# scheda_mot.net
KiCad netlist of a schematic drawn in EAGLE
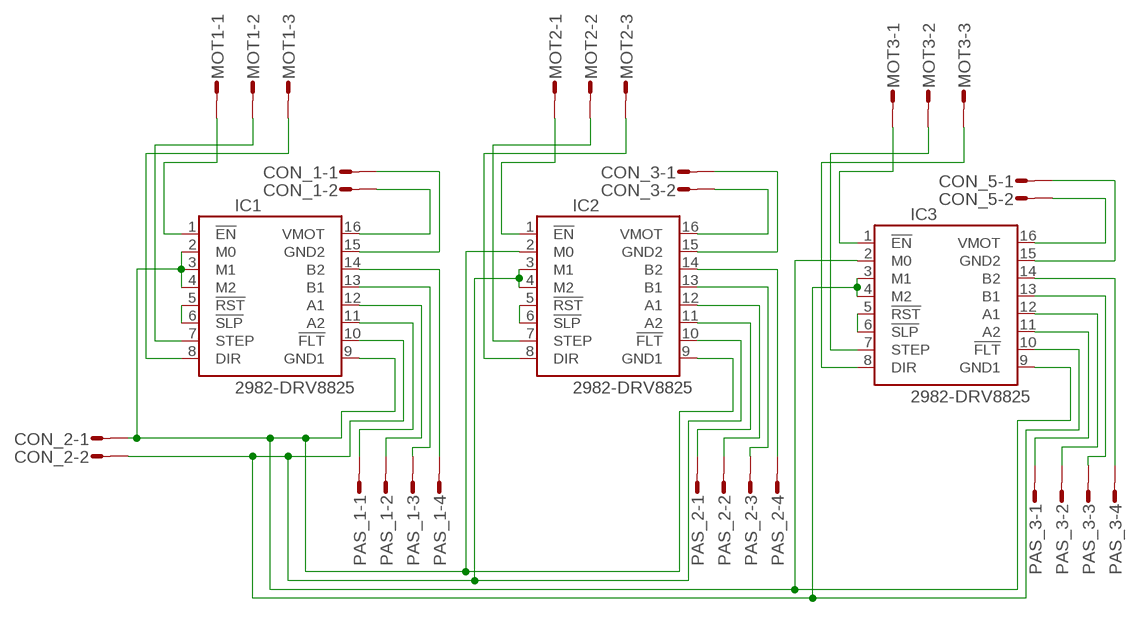
[diagram p0: schematic, sheet 1]

(export (version "E")
  (design (tool "Eeschema 10.0.6"))
  (components
    (comp (ref "CON_1")
      (value "S02P")
      (footprint "eagle-import:S02P")
      (libsource (lib "eagle-import") (part "S02P"))
    )
    (comp (ref "CON_2")
      (value "S02P")
      (footprint "eagle-import:S02P")
      (libsource (lib "eagle-import") (part "S02P"))
    )
    (comp (ref "CON_3")
      (value "S02P")
      (footprint "eagle-import:S02P")
      (libsource (lib "eagle-import") (part "S02P"))
    )
    (comp (ref "CON_5")
      (value "S02P")
      (footprint "eagle-import:S02P")
      (libsource (lib "eagle-import") (part "S02P"))
    )
    (comp (ref "IC1")
      (value "2982-DRV8825")
      (footprint "eagle-import:DRV8825")
      (libsource (lib "eagle-import") (part "2982-DRV8825"))
    )
    (comp (ref "IC2")
      (value "2982-DRV8825")
      (footprint "eagle-import:DRV8825")
      (libsource (lib "eagle-import") (part "2982-DRV8825"))
    )
    (comp (ref "IC3")
      (value "2982-DRV8825")
      (footprint "eagle-import:DRV8825")
      (libsource (lib "eagle-import") (part "2982-DRV8825"))
    )
    (comp (ref "MOT1")
      (value "S03P")
      (footprint "eagle-import:S03P")
      (libsource (lib "eagle-import") (part "S03P"))
    )
    (comp (ref "MOT2")
      (value "S03P")
      (footprint "eagle-import:S03P")
      (libsource (lib "eagle-import") (part "S03P"))
    )
    (comp (ref "MOT3")
      (value "S03P")
      (footprint "eagle-import:S03P")
      (libsource (lib "eagle-import") (part "S03P"))
    )
    (comp (ref "PAS_1")
      (value "S05P")
      (footprint "eagle-import:S05P")
      (libsource (lib "eagle-import") (part "S05P"))
    )
    (comp (ref "PAS_2")
      (value "S05P")
      (footprint "eagle-import:S05P")
      (libsource (lib "eagle-import") (part "S05P"))
    )
    (comp (ref "PAS_3")
      (value "S05P")
      (footprint "eagle-import:S05P")
      (libsource (lib "eagle-import") (part "S05P"))
    )
  )
  (nets
    (net (code "1") (name "Net-(CON_1A-S)") (class "Default")
      (node (ref "CON_1") (pin "1") (pinfunction "S_1") (pintype "passive"))
      (node (ref "IC1") (pin "15") (pinfunction "GND2_15") (pintype "power_in"))
    )
    (net (code "2") (name "Net-(CON_1B-S)") (class "Default")
      (node (ref "CON_1") (pin "2") (pinfunction "S_2") (pintype "passive"))
      (node (ref "IC1") (pin "16") (pinfunction "VMOT_16") (pintype "power_in"))
    )
    (net (code "3") (name "Net-(CON_2A-S)") (class "Default")
      (node (ref "CON_2") (pin "1") (pinfunction "S_1") (pintype "passive"))
      (node (ref "IC1") (pin "2") (pinfunction "M0_2") (pintype "passive"))
      (node (ref "IC1") (pin "3") (pinfunction "M1_3") (pintype "passive"))
      (node (ref "IC1") (pin "4") (pinfunction "M2_4") (pintype "passive"))
      (node (ref "IC1") (pin "9") (pinfunction "GND1_9") (pintype "power_in"))
      (node (ref "IC2") (pin "2") (pinfunction "M0_2") (pintype "passive"))
      (node (ref "IC2") (pin "9") (pinfunction "GND1_9") (pintype "power_in"))
      (node (ref "IC3") (pin "2") (pinfunction "M0_2") (pintype "passive"))
      (node (ref "IC3") (pin "9") (pinfunction "GND1_9") (pintype "power_in"))
    )
    (net (code "4") (name "Net-(CON_2B-S)") (class "Default")
      (node (ref "CON_2") (pin "2") (pinfunction "S_2") (pintype "passive"))
      (node (ref "IC1") (pin "10") (pinfunction "~{FLT}_10") (pintype "open_collector"))
      (node (ref "IC2") (pin "10") (pinfunction "~{FLT}_10") (pintype "open_collector"))
      (node (ref "IC2") (pin "3") (pinfunction "M1_3") (pintype "passive"))
      (node (ref "IC2") (pin "4") (pinfunction "M2_4") (pintype "passive"))
      (node (ref "IC3") (pin "10") (pinfunction "~{FLT}_10") (pintype "open_collector"))
      (node (ref "IC3") (pin "3") (pinfunction "M1_3") (pintype "passive"))
      (node (ref "IC3") (pin "4") (pinfunction "M2_4") (pintype "passive"))
    )
    (net (code "5") (name "Net-(CON_3A-S)") (class "Default")
      (node (ref "CON_3") (pin "1") (pinfunction "S_1") (pintype "passive"))
      (node (ref "IC2") (pin "15") (pinfunction "GND2_15") (pintype "power_in"))
    )
    (net (code "6") (name "Net-(CON_3B-S)") (class "Default")
      (node (ref "CON_3") (pin "2") (pinfunction "S_2") (pintype "passive"))
      (node (ref "IC2") (pin "16") (pinfunction "VMOT_16") (pintype "power_in"))
    )
    (net (code "7") (name "Net-(CON_5A-S)") (class "Default")
      (node (ref "CON_5") (pin "1") (pinfunction "S_1") (pintype "passive"))
      (node (ref "IC3") (pin "15") (pinfunction "GND2_15") (pintype "power_in"))
    )
    (net (code "8") (name "Net-(CON_5B-S)") (class "Default")
      (node (ref "CON_5") (pin "2") (pinfunction "S_2") (pintype "passive"))
      (node (ref "IC3") (pin "16") (pinfunction "VMOT_16") (pintype "power_in"))
    )
    (net (code "9") (name "Net-(IC1-A1)") (class "Default")
      (node (ref "IC1") (pin "12") (pinfunction "A1_12") (pintype "output"))
      (node (ref "PAS_1") (pin "2") (pinfunction "S_2") (pintype "passive"))
    )
    (net (code "10") (name "Net-(IC1-A2)") (class "Default")
      (node (ref "IC1") (pin "11") (pinfunction "A2_11") (pintype "output"))
      (node (ref "PAS_1") (pin "1") (pinfunction "S_1") (pintype "passive"))
    )
    (net (code "11") (name "Net-(IC1-B1)") (class "Default")
      (node (ref "IC1") (pin "13") (pinfunction "B1_13") (pintype "output"))
      (node (ref "PAS_1") (pin "3") (pinfunction "S_3") (pintype "passive"))
    )
    (net (code "12") (name "Net-(IC1-B2)") (class "Default")
      (node (ref "IC1") (pin "14") (pinfunction "B2_14") (pintype "output"))
      (node (ref "PAS_1") (pin "4") (pinfunction "S_4") (pintype "passive"))
    )
    (net (code "13") (name "Net-(IC1-DIR)") (class "Default")
      (node (ref "IC1") (pin "8") (pinfunction "DIR_8") (pintype "input"))
      (node (ref "MOT1") (pin "3") (pinfunction "S_3") (pintype "passive"))
    )
    (net (code "14") (name "Net-(IC1-STEP)") (class "Default")
      (node (ref "IC1") (pin "7") (pinfunction "STEP_7") (pintype "input"))
      (node (ref "MOT1") (pin "2") (pinfunction "S_2") (pintype "passive"))
    )
    (net (code "15") (name "Net-(IC1-~{EN})") (class "Default")
      (node (ref "IC1") (pin "1") (pinfunction "~{EN}_1") (pintype "passive"))
      (node (ref "MOT1") (pin "1") (pinfunction "S_1") (pintype "passive"))
    )
    (net (code "16") (name "Net-(IC1-~{RST})") (class "Default")
      (node (ref "IC1") (pin "5") (pinfunction "~{RST}_5") (pintype "input"))
      (node (ref "IC1") (pin "6") (pinfunction "~{SLP}_6") (pintype "input"))
    )
    (net (code "17") (name "Net-(IC2-A1)") (class "Default")
      (node (ref "IC2") (pin "12") (pinfunction "A1_12") (pintype "output"))
      (node (ref "PAS_2") (pin "2") (pinfunction "S_2") (pintype "passive"))
    )
    (net (code "18") (name "Net-(IC2-A2)") (class "Default")
      (node (ref "IC2") (pin "11") (pinfunction "A2_11") (pintype "output"))
      (node (ref "PAS_2") (pin "1") (pinfunction "S_1") (pintype "passive"))
    )
    (net (code "19") (name "Net-(IC2-B1)") (class "Default")
      (node (ref "IC2") (pin "13") (pinfunction "B1_13") (pintype "output"))
      (node (ref "PAS_2") (pin "3") (pinfunction "S_3") (pintype "passive"))
    )
    (net (code "20") (name "Net-(IC2-B2)") (class "Default")
      (node (ref "IC2") (pin "14") (pinfunction "B2_14") (pintype "output"))
      (node (ref "PAS_2") (pin "4") (pinfunction "S_4") (pintype "passive"))
    )
    (net (code "21") (name "Net-(IC2-DIR)") (class "Default")
      (node (ref "IC2") (pin "8") (pinfunction "DIR_8") (pintype "input"))
      (node (ref "MOT2") (pin "3") (pinfunction "S_3") (pintype "passive"))
    )
    (net (code "22") (name "Net-(IC2-STEP)") (class "Default")
      (node (ref "IC2") (pin "7") (pinfunction "STEP_7") (pintype "input"))
      (node (ref "MOT2") (pin "2") (pinfunction "S_2") (pintype "passive"))
    )
    (net (code "23") (name "Net-(IC2-~{EN})") (class "Default")
      (node (ref "IC2") (pin "1") (pinfunction "~{EN}_1") (pintype "passive"))
      (node (ref "MOT2") (pin "1") (pinfunction "S_1") (pintype "passive"))
    )
    (net (code "24") (name "Net-(IC2-~{RST})") (class "Default")
      (node (ref "IC2") (pin "5") (pinfunction "~{RST}_5") (pintype "input"))
      (node (ref "IC2") (pin "6") (pinfunction "~{SLP}_6") (pintype "input"))
    )
    (net (code "25") (name "Net-(IC3-A1)") (class "Default")
      (node (ref "IC3") (pin "12") (pinfunction "A1_12") (pintype "output"))
      (node (ref "PAS_3") (pin "2") (pinfunction "S_2") (pintype "passive"))
    )
    (net (code "26") (name "Net-(IC3-A2)") (class "Default")
      (node (ref "IC3") (pin "11") (pinfunction "A2_11") (pintype "output"))
      (node (ref "PAS_3") (pin "1") (pinfunction "S_1") (pintype "passive"))
    )
    (net (code "27") (name "Net-(IC3-B1)") (class "Default")
      (node (ref "IC3") (pin "13") (pinfunction "B1_13") (pintype "output"))
      (node (ref "PAS_3") (pin "3") (pinfunction "S_3") (pintype "passive"))
    )
    (net (code "28") (name "Net-(IC3-B2)") (class "Default")
      (node (ref "IC3") (pin "14") (pinfunction "B2_14") (pintype "output"))
      (node (ref "PAS_3") (pin "4") (pinfunction "S_4") (pintype "passive"))
    )
    (net (code "29") (name "Net-(IC3-DIR)") (class "Default")
      (node (ref "IC3") (pin "8") (pinfunction "DIR_8") (pintype "input"))
      (node (ref "MOT3") (pin "3") (pinfunction "S_3") (pintype "passive"))
    )
    (net (code "30") (name "Net-(IC3-STEP)") (class "Default")
      (node (ref "IC3") (pin "7") (pinfunction "STEP_7") (pintype "input"))
      (node (ref "MOT3") (pin "2") (pinfunction "S_2") (pintype "passive"))
    )
    (net (code "31") (name "Net-(IC3-~{EN})") (class "Default")
      (node (ref "IC3") (pin "1") (pinfunction "~{EN}_1") (pintype "passive"))
      (node (ref "MOT3") (pin "1") (pinfunction "S_1") (pintype "passive"))
    )
    (net (code "32") (name "Net-(IC3-~{RST})") (class "Default")
      (node (ref "IC3") (pin "5") (pinfunction "~{RST}_5") (pintype "input"))
      (node (ref "IC3") (pin "6") (pinfunction "~{SLP}_6") (pintype "input"))
    )
  )
)
